# QPA2609.net
KiCad netlist of a schematic drawn in Altium Designer
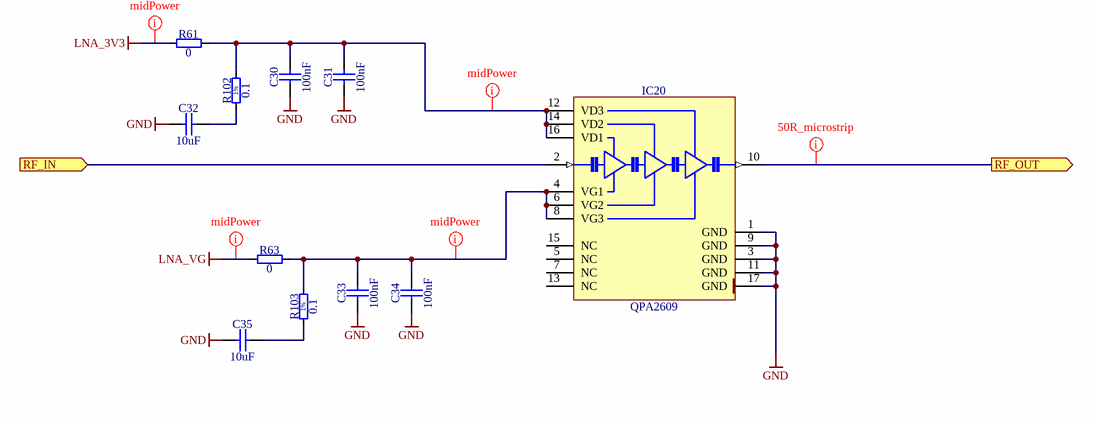
[diagram p0: QPA2609.SchDoc]

(export (version "E")
  (design (tool "Eeschema 10.0.6"))
  (components
    (comp (ref "C30")
      (value "100nF")
      (footprint "CAPC1005X55N")
      (description "Non-polarised capacitor")
      (fields
        (field (name "PART NUMBER") "CC0402_100NF_16V_10%_X7R")
        (field (name "VOLTAGE") "16V")
        (field (name "AUTHOR") "CERN DEM JLC")
      )
      (libsource (lib "Capacitors") (part "Capacitor - non polarized"))
    )
    (comp (ref "C31")
      (value "100nF")
      (footprint "CAPC1005X55N")
      (description "Non-polarised capacitor")
      (fields
        (field (name "PART NUMBER") "CC0402_100NF_16V_10%_X7R")
        (field (name "VOLTAGE") "16V")
        (field (name "AUTHOR") "CERN DEM JLC")
      )
      (libsource (lib "Capacitors") (part "Capacitor - non polarized"))
    )
    (comp (ref "C32")
      (value "10uF")
      (footprint "CAPC2012X135N")
      (description "Non-polarised capacitor")
      (fields
        (field (name "PART NUMBER") "CC0805_10UF_10V_10%_X7R")
        (field (name "VOLTAGE") "10V")
        (field (name "AUTHOR") "CERN DEM JLC")
      )
      (libsource (lib "Capacitors") (part "Capacitor - non polarized"))
    )
    (comp (ref "C33")
      (value "100nF")
      (footprint "CAPC1005X55N")
      (description "Non-polarised capacitor")
      (fields
        (field (name "PART NUMBER") "CC0402_100NF_16V_10%_X7R")
        (field (name "VOLTAGE") "16V")
        (field (name "AUTHOR") "CERN DEM JLC")
      )
      (libsource (lib "Capacitors") (part "Capacitor - non polarized"))
    )
    (comp (ref "C34")
      (value "100nF")
      (footprint "CAPC1005X55N")
      (description "Non-polarised capacitor")
      (fields
        (field (name "PART NUMBER") "CC0402_100NF_16V_10%_X7R")
        (field (name "VOLTAGE") "16V")
        (field (name "AUTHOR") "CERN DEM JLC")
      )
      (libsource (lib "Capacitors") (part "Capacitor - non polarized"))
    )
    (comp (ref "C35")
      (value "10uF")
      (footprint "CAPC2012X135N")
      (description "Non-polarised capacitor")
      (fields
        (field (name "PART NUMBER") "CC0805_10UF_10V_10%_X7R")
        (field (name "VOLTAGE") "10V")
        (field (name "AUTHOR") "CERN DEM JLC")
      )
      (libsource (lib "Capacitors") (part "Capacitor - non polarized"))
    )
    (comp (ref "IC20")
      (value "QPA2609")
      (footprint "QORVO_QPA2609")
      (description "7-14GHz GaAs Low Noise Amplifier")
      (fields (field (name "MANUFACTURER") "QORVO") (field (name "AUTHOR") "CERN DEM JLC"))
      (libsource (lib "ICs And Semiconductors") (part "QPA2609"))
    )
    (comp (ref "R61")
      (value "0")
      (footprint "RESC1608X55N")
      (description "Resistor")
      (fields
        (field (name "PART NUMBER") "R0603_0R_JUMPER")
        (field (name "MANUFACTURER") "GENERIC")
        (field (name "AUTHOR") "CERN DEM JLC")
      )
      (libsource (lib "Resistors") (part "Resistor"))
    )
    (comp (ref "R63")
      (value "0")
      (footprint "RESC1608X55N")
      (description "Resistor")
      (fields
        (field (name "PART NUMBER") "R0603_0R_JUMPER")
        (field (name "MANUFACTURER") "GENERIC")
        (field (name "AUTHOR") "CERN DEM JLC")
      )
      (libsource (lib "Resistors") (part "Resistor"))
    )
    (comp (ref "R102")
      (value "0.1")
      (footprint "RESC1005X40N")
      (description "Resistor - 1%")
      (fields
        (field (name "PART NUMBER") "R0402_0.1R_1%_0.0625W_100PPM")
        (field (name "POWER") "0.0625W")
        (field (name "AUTHOR") "CERN DEM MR")
      )
      (libsource (lib "Resistors") (part "Resistor - 1%"))
    )
    (comp (ref "R103")
      (value "0.1")
      (footprint "RESC1005X40N")
      (description "Resistor - 1%")
      (fields
        (field (name "PART NUMBER") "R0402_0.1R_1%_0.0625W_100PPM")
        (field (name "POWER") "0.0625W")
        (field (name "AUTHOR") "CERN DEM MR")
      )
      (libsource (lib "Resistors") (part "Resistor - 1%"))
    )
  )
  (nets
    (net (code "1") (name "/RF_IN") (class "Default")
      (node (ref "IC20") (pin "2") (pinfunction "RF_IN_2") (pintype "input"))
    )
    (net (code "2") (name "/RF_OUT") (class "Default")
      (node (ref "IC20") (pin "10") (pinfunction "RF_OUT_10") (pintype "output"))
    )
    (net (code "3") (name "GND") (class "Default")
      (node (ref "C30") (pin "1") (pinfunction "1_1") (pintype "passive"))
      (node (ref "C31") (pin "1") (pinfunction "1_1") (pintype "passive"))
      (node (ref "C32") (pin "1") (pinfunction "1_1") (pintype "passive"))
      (node (ref "C33") (pin "1") (pinfunction "1_1") (pintype "passive"))
      (node (ref "C34") (pin "1") (pinfunction "1_1") (pintype "passive"))
      (node (ref "C35") (pin "1") (pinfunction "1_1") (pintype "passive"))
      (node (ref "IC20") (pin "1") (pinfunction "GND_1") (pintype "power_in"))
      (node (ref "IC20") (pin "11") (pinfunction "GND_11") (pintype "power_in"))
      (node (ref "IC20") (pin "17") (pinfunction "GND_17") (pintype "power_in"))
      (node (ref "IC20") (pin "3") (pinfunction "GND_3") (pintype "power_in"))
      (node (ref "IC20") (pin "9") (pinfunction "GND_9") (pintype "power_in"))
    )
    (net (code "4") (name "LNA_3V3") (class "Default")
      (node (ref "R61") (pin "1") (pinfunction "1_1") (pintype "passive"))
    )
    (net (code "5") (name "LNA_VG") (class "Default")
      (node (ref "R63") (pin "1") (pinfunction "1_1") (pintype "passive"))
    )
    (net (code "6") (name "Net-(C32-Pad2)") (class "Default")
      (node (ref "C32") (pin "2") (pinfunction "2_2") (pintype "passive"))
      (node (ref "R102") (pin "1") (pinfunction "1_1") (pintype "passive"))
    )
    (net (code "7") (name "Net-(C35-Pad2)") (class "Default")
      (node (ref "C35") (pin "2") (pinfunction "2_2") (pintype "passive"))
      (node (ref "R103") (pin "1") (pinfunction "1_1") (pintype "passive"))
    )
    (net (code "8") (name "Net-(IC20-VD1)") (class "Default")
      (node (ref "C30") (pin "2") (pinfunction "2_2") (pintype "passive"))
      (node (ref "C31") (pin "2") (pinfunction "2_2") (pintype "passive"))
      (node (ref "IC20") (pin "12") (pinfunction "VD3_12") (pintype "power_in"))
      (node (ref "IC20") (pin "14") (pinfunction "VD2_14") (pintype "power_in"))
      (node (ref "IC20") (pin "16") (pinfunction "VD1_16") (pintype "power_in"))
      (node (ref "R102") (pin "2") (pinfunction "2_2") (pintype "passive"))
      (node (ref "R61") (pin "2") (pinfunction "2_2") (pintype "passive"))
    )
    (net (code "9") (name "Net-(IC20-VG1)") (class "Default")
      (node (ref "C33") (pin "2") (pinfunction "2_2") (pintype "passive"))
      (node (ref "C34") (pin "2") (pinfunction "2_2") (pintype "passive"))
      (node (ref "IC20") (pin "4") (pinfunction "VG1_4") (pintype "power_in"))
      (node (ref "IC20") (pin "6") (pinfunction "VG2_6") (pintype "power_in"))
      (node (ref "IC20") (pin "8") (pinfunction "VG3_8") (pintype "power_in"))
      (node (ref "R103") (pin "2") (pinfunction "2_2") (pintype "passive"))
      (node (ref "R63") (pin "2") (pinfunction "2_2") (pintype "passive"))
    )
    (net (code "10") (name "unconnected-(IC20-NC-Pad5)") (class "Default")
      (node (ref "IC20") (pin "5") (pinfunction "NC_5") (pintype "passive"))
    )
    (net (code "11") (name "unconnected-(IC20-NC-Pad7)") (class "Default")
      (node (ref "IC20") (pin "7") (pinfunction "NC_7") (pintype "power_in"))
    )
    (net (code "12") (name "unconnected-(IC20-NC-Pad13)") (class "Default")
      (node (ref "IC20") (pin "13") (pinfunction "NC_13") (pintype "passive"))
    )
    (net (code "13") (name "unconnected-(IC20-NC-Pad15)") (class "Default")
      (node (ref "IC20") (pin "15") (pinfunction "NC_15") (pintype "passive"))
    )
  )
)
